# SSR_IO_LOGIC.net
KiCad netlist of a schematic drawn in Altium Designer
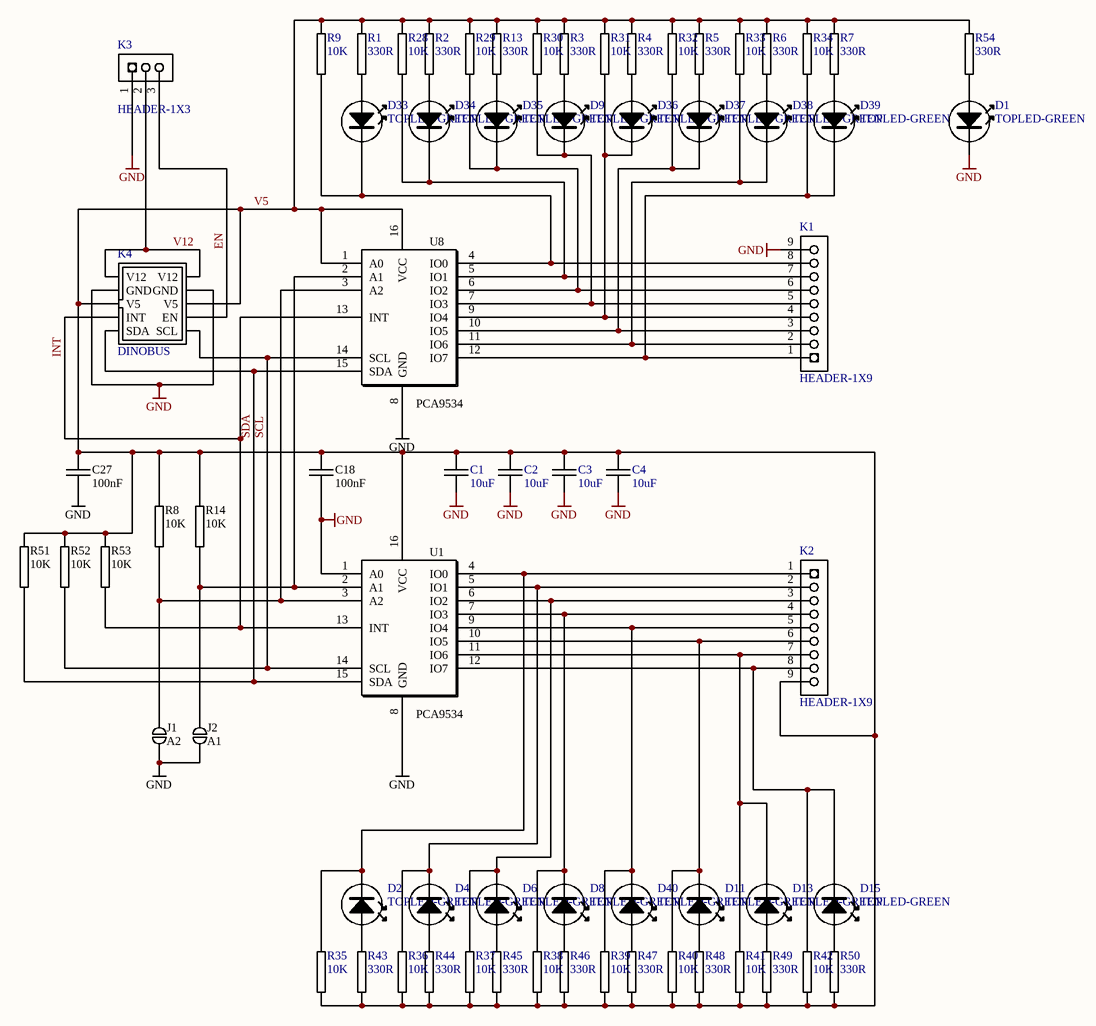
[diagram p0: SSR IO LOGIC.SchDoc]

(export (version "E")
  (design (tool "Eeschema 10.0.6"))
  (components
    (comp (ref "C1")
      (value "10uF")
      (footprint "0805C-GENERIC")
      (description "CAPACITOR 0805 CERAMIC")
      (fields
        (field (name "MANUFACTURER PART NUMBER") "C2012X5R1C106M")
        (field (name "MANUFACTURER") "TDK Corporation")
      )
      (libsource (lib "vh_Altium Library") (part "0805C-10UF-16V-X5R-TDK"))
    )
    (comp (ref "C2")
      (value "10uF")
      (footprint "0805C-GENERIC")
      (description "CAPACITOR 0805 CERAMIC")
      (fields
        (field (name "MANUFACTURER PART NUMBER") "C2012X5R1C106M")
        (field (name "MANUFACTURER") "TDK Corporation")
      )
      (libsource (lib "vh_Altium Library") (part "0805C-10UF-16V-X5R-TDK"))
    )
    (comp (ref "C3")
      (value "10uF")
      (footprint "0805C-GENERIC")
      (description "CAPACITOR 0805 CERAMIC")
      (fields
        (field (name "MANUFACTURER PART NUMBER") "C2012X5R1C106M")
        (field (name "MANUFACTURER") "TDK Corporation")
      )
      (libsource (lib "vh_Altium Library") (part "0805C-10UF-16V-X5R-TDK"))
    )
    (comp (ref "C4")
      (value "10uF")
      (footprint "0805C-GENERIC")
      (description "CAPACITOR 0805 CERAMIC")
      (fields
        (field (name "MANUFACTURER PART NUMBER") "C2012X5R1C106M")
        (field (name "MANUFACTURER") "TDK Corporation")
      )
      (libsource (lib "vh_Altium Library") (part "0805C-10UF-16V-X5R-TDK"))
    )
    (comp (ref "C18")
      (value "100nF")
      (footprint "0805C")
      (description "CAPACITOR NONPOLARISED")
      (libsource (lib "I2Csticks") (part "0805C-100NF"))
    )
    (comp (ref "C27")
      (value "100nF")
      (footprint "0805C")
      (description "CAPACITOR NONPOLARISED")
      (libsource (lib "I2Csticks") (part "0805C-100NF"))
    )
    (comp (ref "D1")
      (value "TOPLED-GREEN")
      (footprint "TOPLED-GREEN")
      (libsource (lib "vh_Altium Library") (part "TOPLED-GREEN"))
    )
    (comp (ref "D2")
      (value "TOPLED-GREEN")
      (footprint "TOPLED-GREEN")
      (libsource (lib "vh_Altium Library") (part "TOPLED-GREEN"))
    )
    (comp (ref "D4")
      (value "TOPLED-GREEN")
      (footprint "TOPLED-GREEN")
      (libsource (lib "vh_Altium Library") (part "TOPLED-GREEN"))
    )
    (comp (ref "D6")
      (value "TOPLED-GREEN")
      (footprint "TOPLED-GREEN")
      (libsource (lib "vh_Altium Library") (part "TOPLED-GREEN"))
    )
    (comp (ref "D8")
      (value "TOPLED-GREEN")
      (footprint "TOPLED-GREEN")
      (libsource (lib "vh_Altium Library") (part "TOPLED-GREEN"))
    )
    (comp (ref "D9")
      (value "TOPLED-GREEN")
      (footprint "TOPLED-GREEN")
      (libsource (lib "vh_Altium Library") (part "TOPLED-GREEN"))
    )
    (comp (ref "D11")
      (value "TOPLED-GREEN")
      (footprint "TOPLED-GREEN")
      (libsource (lib "vh_Altium Library") (part "TOPLED-GREEN"))
    )
    (comp (ref "D13")
      (value "TOPLED-GREEN")
      (footprint "TOPLED-GREEN")
      (libsource (lib "vh_Altium Library") (part "TOPLED-GREEN"))
    )
    (comp (ref "D15")
      (value "TOPLED-GREEN")
      (footprint "TOPLED-GREEN")
      (libsource (lib "vh_Altium Library") (part "TOPLED-GREEN"))
    )
    (comp (ref "D33")
      (value "TOPLED-GREEN")
      (footprint "TOPLED-GREEN")
      (libsource (lib "vh_Altium Library") (part "TOPLED-GREEN"))
    )
    (comp (ref "D34")
      (value "TOPLED-GREEN")
      (footprint "TOPLED-GREEN")
      (libsource (lib "vh_Altium Library") (part "TOPLED-GREEN"))
    )
    (comp (ref "D35")
      (value "TOPLED-GREEN")
      (footprint "TOPLED-GREEN")
      (libsource (lib "vh_Altium Library") (part "TOPLED-GREEN"))
    )
    (comp (ref "D36")
      (value "TOPLED-GREEN")
      (footprint "TOPLED-GREEN")
      (libsource (lib "vh_Altium Library") (part "TOPLED-GREEN"))
    )
    (comp (ref "D37")
      (value "TOPLED-GREEN")
      (footprint "TOPLED-GREEN")
      (libsource (lib "vh_Altium Library") (part "TOPLED-GREEN"))
    )
    (comp (ref "D38")
      (value "TOPLED-GREEN")
      (footprint "TOPLED-GREEN")
      (libsource (lib "vh_Altium Library") (part "TOPLED-GREEN"))
    )
    (comp (ref "D39")
      (value "TOPLED-GREEN")
      (footprint "TOPLED-GREEN")
      (libsource (lib "vh_Altium Library") (part "TOPLED-GREEN"))
    )
    (comp (ref "D40")
      (value "TOPLED-GREEN")
      (footprint "TOPLED-GREEN")
      (libsource (lib "vh_Altium Library") (part "TOPLED-GREEN"))
    )
    (comp (ref "J1") (value "A2") (footprint "BYPASS") (libsource (lib "*") (part "BYPASS")))
    (comp (ref "J2") (value "A1") (footprint "BYPASS") (libsource (lib "*") (part "BYPASS")))
    (comp (ref "K1")
      (value "HEADER-1X9")
      (footprint "HEADER-1X9")
      (libsource (lib "vh_Altium Library") (part "HEADER-1X9"))
    )
    (comp (ref "K2")
      (value "HEADER-1X9")
      (footprint "HEADER-1X9")
      (libsource (lib "vh_Altium Library") (part "HEADER-1X9"))
    )
    (comp (ref "K3")
      (value "HEADER-1X3")
      (footprint "HEADER-1X3")
      (libsource (lib "vh_Altium Library") (part "HEADER-1X3"))
    )
    (comp (ref "K4")
      (value "DINOBUS")
      (footprint "IDC10-B")
      (description "CONN HEADER LOW-PRO 10POS GOLD")
      (fields (field (name "MANUFACTURER") "Assmann Electronics Inc"))
      (libsource (lib "Schlib1") (part "DINOBUS"))
    )
    (comp (ref "R1")
      (value "330R")
      (footprint "0805R-330")
      (description "RESISTOR 0805 1/4 WATT THIN FILM")
      (libsource (lib "vh_Altium Library") (part "0805R-330"))
    )
    (comp (ref "R2")
      (value "330R")
      (footprint "0805R-330")
      (description "RESISTOR 0805 1/4 WATT THIN FILM")
      (libsource (lib "vh_Altium Library") (part "0805R-330"))
    )
    (comp (ref "R3")
      (value "330R")
      (footprint "0805R-330")
      (description "RESISTOR 0805 1/4 WATT THIN FILM")
      (libsource (lib "vh_Altium Library") (part "0805R-330"))
    )
    (comp (ref "R4")
      (value "330R")
      (footprint "0805R-330")
      (description "RESISTOR 0805 1/4 WATT THIN FILM")
      (libsource (lib "vh_Altium Library") (part "0805R-330"))
    )
    (comp (ref "R5")
      (value "330R")
      (footprint "0805R-330")
      (description "RESISTOR 0805 1/4 WATT THIN FILM")
      (libsource (lib "vh_Altium Library") (part "0805R-330"))
    )
    (comp (ref "R6")
      (value "330R")
      (footprint "0805R-330")
      (description "RESISTOR 0805 1/4 WATT THIN FILM")
      (libsource (lib "vh_Altium Library") (part "0805R-330"))
    )
    (comp (ref "R7")
      (value "330R")
      (footprint "0805R-330")
      (description "RESISTOR 0805 1/4 WATT THIN FILM")
      (libsource (lib "vh_Altium Library") (part "0805R-330"))
    )
    (comp (ref "R8")
      (value "10K")
      (footprint "0805R")
      (description "RESISTOR VALUE AS INDICATED")
      (libsource (lib "I2Csticks") (part "0805R-10K"))
    )
    (comp (ref "R9")
      (value "10K")
      (footprint "0805R-10K")
      (description "RESISTOR 0805 1/4 WATT THIN FILM")
      (libsource (lib "vh_Altium Library") (part "0805R-10K"))
    )
    (comp (ref "R13")
      (value "330R")
      (footprint "0805R-330")
      (description "RESISTOR 0805 1/4 WATT THIN FILM")
      (libsource (lib "vh_Altium Library") (part "0805R-330"))
    )
    (comp (ref "R14")
      (value "10K")
      (footprint "0805R")
      (description "RESISTOR VALUE AS INDICATED")
      (libsource (lib "I2Csticks") (part "0805R-10K"))
    )
    (comp (ref "R28")
      (value "10K")
      (footprint "0805R-10K")
      (description "RESISTOR 0805 1/4 WATT THIN FILM")
      (libsource (lib "vh_Altium Library") (part "0805R-10K"))
    )
    (comp (ref "R29")
      (value "10K")
      (footprint "0805R-10K")
      (description "RESISTOR 0805 1/4 WATT THIN FILM")
      (libsource (lib "vh_Altium Library") (part "0805R-10K"))
    )
    (comp (ref "R30")
      (value "10K")
      (footprint "0805R-10K")
      (description "RESISTOR 0805 1/4 WATT THIN FILM")
      (libsource (lib "vh_Altium Library") (part "0805R-10K"))
    )
    (comp (ref "R31")
      (value "10K")
      (footprint "0805R-10K")
      (description "RESISTOR 0805 1/4 WATT THIN FILM")
      (libsource (lib "vh_Altium Library") (part "0805R-10K"))
    )
    (comp (ref "R32")
      (value "10K")
      (footprint "0805R-10K")
      (description "RESISTOR 0805 1/4 WATT THIN FILM")
      (libsource (lib "vh_Altium Library") (part "0805R-10K"))
    )
    (comp (ref "R33")
      (value "10K")
      (footprint "0805R-10K")
      (description "RESISTOR 0805 1/4 WATT THIN FILM")
      (libsource (lib "vh_Altium Library") (part "0805R-10K"))
    )
    (comp (ref "R34")
      (value "10K")
      (footprint "0805R-10K")
      (description "RESISTOR 0805 1/4 WATT THIN FILM")
      (libsource (lib "vh_Altium Library") (part "0805R-10K"))
    )
    (comp (ref "R35")
      (value "10K")
      (footprint "0805R-10K")
      (description "RESISTOR 0805 1/4 WATT THIN FILM")
      (libsource (lib "vh_Altium Library") (part "0805R-10K"))
    )
    (comp (ref "R36")
      (value "10K")
      (footprint "0805R-10K")
      (description "RESISTOR 0805 1/4 WATT THIN FILM")
      (libsource (lib "vh_Altium Library") (part "0805R-10K"))
    )
    (comp (ref "R37")
      (value "10K")
      (footprint "0805R-10K")
      (description "RESISTOR 0805 1/4 WATT THIN FILM")
      (libsource (lib "vh_Altium Library") (part "0805R-10K"))
    )
    (comp (ref "R38")
      (value "10K")
      (footprint "0805R-10K")
      (description "RESISTOR 0805 1/4 WATT THIN FILM")
      (libsource (lib "vh_Altium Library") (part "0805R-10K"))
    )
    (comp (ref "R39")
      (value "10K")
      (footprint "0805R-10K")
      (description "RESISTOR 0805 1/4 WATT THIN FILM")
      (libsource (lib "vh_Altium Library") (part "0805R-10K"))
    )
    (comp (ref "R40")
      (value "10K")
      (footprint "0805R-10K")
      (description "RESISTOR 0805 1/4 WATT THIN FILM")
      (libsource (lib "vh_Altium Library") (part "0805R-10K"))
    )
    (comp (ref "R41")
      (value "10K")
      (footprint "0805R-10K")
      (description "RESISTOR 0805 1/4 WATT THIN FILM")
      (libsource (lib "vh_Altium Library") (part "0805R-10K"))
    )
    (comp (ref "R42")
      (value "10K")
      (footprint "0805R-10K")
      (description "RESISTOR 0805 1/4 WATT THIN FILM")
      (libsource (lib "vh_Altium Library") (part "0805R-10K"))
    )
    (comp (ref "R43")
      (value "330R")
      (footprint "0805R-330")
      (description "RESISTOR 0805 1/4 WATT THIN FILM")
      (libsource (lib "vh_Altium Library") (part "0805R-330"))
    )
    (comp (ref "R44")
      (value "330R")
      (footprint "0805R-330")
      (description "RESISTOR 0805 1/4 WATT THIN FILM")
      (libsource (lib "vh_Altium Library") (part "0805R-330"))
    )
    (comp (ref "R45")
      (value "330R")
      (footprint "0805R-330")
      (description "RESISTOR 0805 1/4 WATT THIN FILM")
      (libsource (lib "vh_Altium Library") (part "0805R-330"))
    )
    (comp (ref "R46")
      (value "330R")
      (footprint "0805R-330")
      (description "RESISTOR 0805 1/4 WATT THIN FILM")
      (libsource (lib "vh_Altium Library") (part "0805R-330"))
    )
    (comp (ref "R47")
      (value "330R")
      (footprint "0805R-330")
      (description "RESISTOR 0805 1/4 WATT THIN FILM")
      (libsource (lib "vh_Altium Library") (part "0805R-330"))
    )
    (comp (ref "R48")
      (value "330R")
      (footprint "0805R-330")
      (description "RESISTOR 0805 1/4 WATT THIN FILM")
      (libsource (lib "vh_Altium Library") (part "0805R-330"))
    )
    (comp (ref "R49")
      (value "330R")
      (footprint "0805R-330")
      (description "RESISTOR 0805 1/4 WATT THIN FILM")
      (libsource (lib "vh_Altium Library") (part "0805R-330"))
    )
    (comp (ref "R50")
      (value "330R")
      (footprint "0805R-330")
      (description "RESISTOR 0805 1/4 WATT THIN FILM")
      (libsource (lib "vh_Altium Library") (part "0805R-330"))
    )
    (comp (ref "R51")
      (value "10K")
      (footprint "0805R")
      (description "RESISTOR VALUE AS INDICATED")
      (libsource (lib "I2Csticks") (part "0805R-10K"))
    )
    (comp (ref "R52")
      (value "10K")
      (footprint "0805R")
      (description "RESISTOR VALUE AS INDICATED")
      (libsource (lib "I2Csticks") (part "0805R-10K"))
    )
    (comp (ref "R53")
      (value "10K")
      (footprint "0805R")
      (description "RESISTOR VALUE AS INDICATED")
      (libsource (lib "I2Csticks") (part "0805R-10K"))
    )
    (comp (ref "R54")
      (value "330R")
      (footprint "0805R-330")
      (description "RESISTOR 0805 1/4 WATT THIN FILM")
      (libsource (lib "vh_Altium Library") (part "0805R-330"))
    )
    (comp (ref "U1")
      (value "PCA9534")
      (footprint "SO16W")
      (description "OCTAL PUSH PULL DRIVER I2C")
      (libsource (lib "*") (part "PCA9534"))
    )
    (comp (ref "U8")
      (value "PCA9534")
      (footprint "SO16W")
      (description "OCTAL PUSH PULL DRIVER I2C")
      (libsource (lib "*") (part "PCA9534"))
    )
  )
  (nets
    (net (code "1") (name "/EN") (class "Default")
      (node (ref "K3") (pin "3") (pintype "passive"))
      (node (ref "K4") (pin "8") (pinfunction "EN_8") (pintype "passive"))
    )
    (net (code "2") (name "/INT") (class "Default")
      (node (ref "K4") (pin "7") (pinfunction "INT_7") (pintype "passive"))
      (node (ref "R53") (pin "1") (pintype "passive"))
      (node (ref "U1") (pin "13") (pinfunction "INT_13") (pintype "passive"))
      (node (ref "U8") (pin "13") (pinfunction "INT_13") (pintype "passive"))
    )
    (net (code "3") (name "/SCL") (class "Default")
      (node (ref "K4") (pin "10") (pinfunction "SCL_10") (pintype "passive"))
      (node (ref "R52") (pin "1") (pintype "passive"))
      (node (ref "U1") (pin "14") (pinfunction "SCL_14") (pintype "passive"))
      (node (ref "U8") (pin "14") (pinfunction "SCL_14") (pintype "passive"))
    )
    (net (code "4") (name "/SDA") (class "Default")
      (node (ref "K4") (pin "9") (pinfunction "SDA_9") (pintype "passive"))
      (node (ref "R51") (pin "1") (pintype "passive"))
      (node (ref "U1") (pin "15") (pinfunction "SDA_15") (pintype "passive"))
      (node (ref "U8") (pin "15") (pinfunction "SDA_15") (pintype "passive"))
    )
    (net (code "5") (name "/V5") (class "Default")
      (node (ref "C1") (pin "1") (pintype "passive"))
      (node (ref "C18") (pin "1") (pintype "passive"))
      (node (ref "C2") (pin "1") (pintype "passive"))
      (node (ref "C27") (pin "1") (pintype "passive"))
      (node (ref "C3") (pin "1") (pintype "passive"))
      (node (ref "C4") (pin "1") (pintype "passive"))
      (node (ref "K2") (pin "9") (pintype "passive"))
      (node (ref "K4") (pin "5") (pinfunction "V5_5") (pintype "passive"))
      (node (ref "K4") (pin "6") (pinfunction "V5_6") (pintype "passive"))
      (node (ref "R1") (pin "2") (pintype "passive"))
      (node (ref "R13") (pin "2") (pintype "passive"))
      (node (ref "R14") (pin "2") (pintype "passive"))
      (node (ref "R2") (pin "2") (pintype "passive"))
      (node (ref "R28") (pin "2") (pintype "passive"))
      (node (ref "R29") (pin "2") (pintype "passive"))
      (node (ref "R3") (pin "2") (pintype "passive"))
      (node (ref "R30") (pin "2") (pintype "passive"))
      (node (ref "R31") (pin "2") (pintype "passive"))
      (node (ref "R32") (pin "2") (pintype "passive"))
      (node (ref "R33") (pin "2") (pintype "passive"))
      (node (ref "R34") (pin "2") (pintype "passive"))
      (node (ref "R35") (pin "2") (pintype "passive"))
      (node (ref "R36") (pin "2") (pintype "passive"))
      (node (ref "R37") (pin "2") (pintype "passive"))
      (node (ref "R38") (pin "2") (pintype "passive"))
      (node (ref "R39") (pin "2") (pintype "passive"))
      (node (ref "R4") (pin "2") (pintype "passive"))
      (node (ref "R40") (pin "2") (pintype "passive"))
      (node (ref "R41") (pin "2") (pintype "passive"))
      (node (ref "R42") (pin "2") (pintype "passive"))
      (node (ref "R43") (pin "2") (pintype "passive"))
      (node (ref "R44") (pin "2") (pintype "passive"))
      (node (ref "R45") (pin "2") (pintype "passive"))
      (node (ref "R46") (pin "2") (pintype "passive"))
      (node (ref "R47") (pin "2") (pintype "passive"))
      (node (ref "R48") (pin "2") (pintype "passive"))
      (node (ref "R49") (pin "2") (pintype "passive"))
      (node (ref "R5") (pin "2") (pintype "passive"))
      (node (ref "R50") (pin "2") (pintype "passive"))
      (node (ref "R51") (pin "2") (pintype "passive"))
      (node (ref "R52") (pin "2") (pintype "passive"))
      (node (ref "R53") (pin "2") (pintype "passive"))
      (node (ref "R54") (pin "2") (pintype "passive"))
      (node (ref "R6") (pin "2") (pintype "passive"))
      (node (ref "R7") (pin "2") (pintype "passive"))
      (node (ref "R8") (pin "2") (pintype "passive"))
      (node (ref "R9") (pin "2") (pintype "passive"))
      (node (ref "U1") (pin "16") (pinfunction "VCC_16") (pintype "passive"))
      (node (ref "U8") (pin "1") (pinfunction "A0_1") (pintype "passive"))
      (node (ref "U8") (pin "16") (pinfunction "VCC_16") (pintype "passive"))
    )
    (net (code "6") (name "/V12") (class "Default")
      (node (ref "K3") (pin "2") (pintype "passive"))
      (node (ref "K4") (pin "1") (pinfunction "V12_1") (pintype "passive"))
      (node (ref "K4") (pin "2") (pinfunction "V12_2") (pintype "passive"))
    )
    (net (code "7") (name "GND") (class "Default")
      (node (ref "C1") (pin "2") (pintype "passive"))
      (node (ref "C18") (pin "2") (pintype "passive"))
      (node (ref "C2") (pin "2") (pintype "passive"))
      (node (ref "C27") (pin "2") (pintype "passive"))
      (node (ref "C3") (pin "2") (pintype "passive"))
      (node (ref "C4") (pin "2") (pintype "passive"))
      (node (ref "D1") (pin "K") (pintype "passive"))
      (node (ref "J1") (pin "2") (pinfunction "2_2") (pintype "passive"))
      (node (ref "J2") (pin "2") (pinfunction "2_2") (pintype "passive"))
      (node (ref "K1") (pin "9") (pintype "passive"))
      (node (ref "K3") (pin "1") (pintype "passive"))
      (node (ref "K4") (pin "3") (pinfunction "GND_3") (pintype "passive"))
      (node (ref "K4") (pin "4") (pinfunction "GND_4") (pintype "passive"))
      (node (ref "U1") (pin "1") (pinfunction "A0_1") (pintype "passive"))
      (node (ref "U1") (pin "8") (pinfunction "GND_8") (pintype "passive"))
      (node (ref "U8") (pin "8") (pinfunction "GND_8") (pintype "passive"))
    )
    (net (code "8") (name "Net-(D1-PadA)") (class "Default")
      (node (ref "D1") (pin "A") (pintype "passive"))
      (node (ref "R54") (pin "1") (pintype "passive"))
    )
    (net (code "9") (name "Net-(D2-PadA)") (class "Default")
      (node (ref "D2") (pin "A") (pintype "passive"))
      (node (ref "R43") (pin "1") (pintype "passive"))
    )
    (net (code "10") (name "Net-(D4-PadA)") (class "Default")
      (node (ref "D4") (pin "A") (pintype "passive"))
      (node (ref "R44") (pin "1") (pintype "passive"))
    )
    (net (code "11") (name "Net-(D6-PadA)") (class "Default")
      (node (ref "D6") (pin "A") (pintype "passive"))
      (node (ref "R45") (pin "1") (pintype "passive"))
    )
    (net (code "12") (name "Net-(D8-PadA)") (class "Default")
      (node (ref "D8") (pin "A") (pintype "passive"))
      (node (ref "R46") (pin "1") (pintype "passive"))
    )
    (net (code "13") (name "Net-(D9-PadA)") (class "Default")
      (node (ref "D9") (pin "A") (pintype "passive"))
      (node (ref "R3") (pin "1") (pintype "passive"))
    )
    (net (code "14") (name "Net-(D11-PadA)") (class "Default")
      (node (ref "D11") (pin "A") (pintype "passive"))
      (node (ref "R48") (pin "1") (pintype "passive"))
    )
    (net (code "15") (name "Net-(D13-PadA)") (class "Default")
      (node (ref "D13") (pin "A") (pintype "passive"))
      (node (ref "R49") (pin "1") (pintype "passive"))
    )
    (net (code "16") (name "Net-(D15-PadA)") (class "Default")
      (node (ref "D15") (pin "A") (pintype "passive"))
      (node (ref "R50") (pin "1") (pintype "passive"))
    )
    (net (code "17") (name "Net-(D33-PadA)") (class "Default")
      (node (ref "D33") (pin "A") (pintype "passive"))
      (node (ref "R1") (pin "1") (pintype "passive"))
    )
    (net (code "18") (name "Net-(D34-PadA)") (class "Default")
      (node (ref "D34") (pin "A") (pintype "passive"))
      (node (ref "R2") (pin "1") (pintype "passive"))
    )
    (net (code "19") (name "Net-(D35-PadA)") (class "Default")
      (node (ref "D35") (pin "A") (pintype "passive"))
      (node (ref "R13") (pin "1") (pintype "passive"))
    )
    (net (code "20") (name "Net-(D36-PadA)") (class "Default")
      (node (ref "D36") (pin "A") (pintype "passive"))
      (node (ref "R4") (pin "1") (pintype "passive"))
    )
    (net (code "21") (name "Net-(D37-PadA)") (class "Default")
      (node (ref "D37") (pin "A") (pintype "passive"))
      (node (ref "R5") (pin "1") (pintype "passive"))
    )
    (net (code "22") (name "Net-(D38-PadA)") (class "Default")
      (node (ref "D38") (pin "A") (pintype "passive"))
      (node (ref "R6") (pin "1") (pintype "passive"))
    )
    (net (code "23") (name "Net-(D39-PadA)") (class "Default")
      (node (ref "D39") (pin "A") (pintype "passive"))
      (node (ref "R7") (pin "1") (pintype "passive"))
    )
    (net (code "24") (name "Net-(D40-PadA)") (class "Default")
      (node (ref "D40") (pin "A") (pintype "passive"))
      (node (ref "R47") (pin "1") (pintype "passive"))
    )
    (net (code "25") (name "Net-(U1-A1)") (class "Default")
      (node (ref "J2") (pin "1") (pinfunction "1_1") (pintype "passive"))
      (node (ref "R14") (pin "1") (pintype "passive"))
      (node (ref "U1") (pin "2") (pinfunction "A1_2") (pintype "passive"))
      (node (ref "U8") (pin "2") (pinfunction "A1_2") (pintype "passive"))
    )
    (net (code "26") (name "Net-(U1-A2)") (class "Default")
      (node (ref "J1") (pin "1") (pinfunction "1_1") (pintype "passive"))
      (node (ref "R8") (pin "1") (pintype "passive"))
      (node (ref "U1") (pin "3") (pinfunction "A2_3") (pintype "passive"))
      (node (ref "U8") (pin "3") (pinfunction "A2_3") (pintype "passive"))
    )
    (net (code "27") (name "Net-(U1-IO0)") (class "Default")
      (node (ref "D2") (pin "K") (pintype "passive"))
      (node (ref "K2") (pin "1") (pintype "passive"))
      (node (ref "R35") (pin "1") (pintype "passive"))
      (node (ref "U1") (pin "4") (pinfunction "IO0_4") (pintype "passive"))
    )
    (net (code "28") (name "Net-(U1-IO1)") (class "Default")
      (node (ref "D4") (pin "K") (pintype "passive"))
      (node (ref "K2") (pin "2") (pintype "passive"))
      (node (ref "R36") (pin "1") (pintype "passive"))
      (node (ref "U1") (pin "5") (pinfunction "IO1_5") (pintype "passive"))
    )
    (net (code "29") (name "Net-(U1-IO2)") (class "Default")
      (node (ref "D6") (pin "K") (pintype "passive"))
      (node (ref "K2") (pin "3") (pintype "passive"))
      (node (ref "R37") (pin "1") (pintype "passive"))
      (node (ref "U1") (pin "6") (pinfunction "IO2_6") (pintype "passive"))
    )
    (net (code "30") (name "Net-(U1-IO3)") (class "Default")
      (node (ref "D8") (pin "K") (pintype "passive"))
      (node (ref "K2") (pin "4") (pintype "passive"))
      (node (ref "R38") (pin "1") (pintype "passive"))
      (node (ref "U1") (pin "7") (pinfunction "IO3_7") (pintype "passive"))
    )
    (net (code "31") (name "Net-(U1-IO4)") (class "Default")
      (node (ref "D40") (pin "K") (pintype "passive"))
      (node (ref "K2") (pin "5") (pintype "passive"))
      (node (ref "R39") (pin "1") (pintype "passive"))
      (node (ref "U1") (pin "9") (pinfunction "IO4_9") (pintype "passive"))
    )
    (net (code "32") (name "Net-(U1-IO5)") (class "Default")
      (node (ref "D11") (pin "K") (pintype "passive"))
      (node (ref "K2") (pin "6") (pintype "passive"))
      (node (ref "R40") (pin "1") (pintype "passive"))
      (node (ref "U1") (pin "10") (pinfunction "IO5_10") (pintype "passive"))
    )
    (net (code "33") (name "Net-(U1-IO6)") (class "Default")
      (node (ref "D13") (pin "K") (pintype "passive"))
      (node (ref "K2") (pin "7") (pintype "passive"))
      (node (ref "R41") (pin "1") (pintype "passive"))
      (node (ref "U1") (pin "11") (pinfunction "IO6_11") (pintype "passive"))
    )
    (net (code "34") (name "Net-(U1-IO7)") (class "Default")
      (node (ref "D15") (pin "K") (pintype "passive"))
      (node (ref "K2") (pin "8") (pintype "passive"))
      (node (ref "R42") (pin "1") (pintype "passive"))
      (node (ref "U1") (pin "12") (pinfunction "IO7_12") (pintype "passive"))
    )
    (net (code "35") (name "Net-(U8-IO0)") (class "Default")
      (node (ref "D33") (pin "K") (pintype "passive"))
      (node (ref "K1") (pin "8") (pintype "passive"))
      (node (ref "R9") (pin "1") (pintype "passive"))
      (node (ref "U8") (pin "4") (pinfunction "IO0_4") (pintype "passive"))
    )
    (net (code "36") (name "Net-(U8-IO1)") (class "Default")
      (node (ref "D34") (pin "K") (pintype "passive"))
      (node (ref "K1") (pin "7") (pintype "passive"))
      (node (ref "R28") (pin "1") (pintype "passive"))
      (node (ref "U8") (pin "5") (pinfunction "IO1_5") (pintype "passive"))
    )
    (net (code "37") (name "Net-(U8-IO2)") (class "Default")
      (node (ref "D35") (pin "K") (pintype "passive"))
      (node (ref "K1") (pin "6") (pintype "passive"))
      (node (ref "R29") (pin "1") (pintype "passive"))
      (node (ref "U8") (pin "6") (pinfunction "IO2_6") (pintype "passive"))
    )
    (net (code "38") (name "Net-(U8-IO3)") (class "Default")
      (node (ref "D9") (pin "K") (pintype "passive"))
      (node (ref "K1") (pin "5") (pintype "passive"))
      (node (ref "R30") (pin "1") (pintype "passive"))
      (node (ref "U8") (pin "7") (pinfunction "IO3_7") (pintype "passive"))
    )
    (net (code "39") (name "Net-(U8-IO4)") (class "Default")
      (node (ref "D36") (pin "K") (pintype "passive"))
      (node (ref "K1") (pin "4") (pintype "passive"))
      (node (ref "R31") (pin "1") (pintype "passive"))
      (node (ref "U8") (pin "9") (pinfunction "IO4_9") (pintype "passive"))
    )
    (net (code "40") (name "Net-(U8-IO5)") (class "Default")
      (node (ref "D37") (pin "K") (pintype "passive"))
      (node (ref "K1") (pin "3") (pintype "passive"))
      (node (ref "R32") (pin "1") (pintype "passive"))
      (node (ref "U8") (pin "10") (pinfunction "IO5_10") (pintype "passive"))
    )
    (net (code "41") (name "Net-(U8-IO6)") (class "Default")
      (node (ref "D38") (pin "K") (pintype "passive"))
      (node (ref "K1") (pin "2") (pintype "passive"))
      (node (ref "R33") (pin "1") (pintype "passive"))
      (node (ref "U8") (pin "11") (pinfunction "IO6_11") (pintype "passive"))
    )
    (net (code "42") (name "Net-(U8-IO7)") (class "Default")
      (node (ref "D39") (pin "K") (pintype "passive"))
      (node (ref "K1") (pin "1") (pintype "passive"))
      (node (ref "R34") (pin "1") (pintype "passive"))
      (node (ref "U8") (pin "12") (pinfunction "IO7_12") (pintype "passive"))
    )
  )
)
